# Channel_supply.net
KiCad netlist of a schematic drawn in Altium Designer
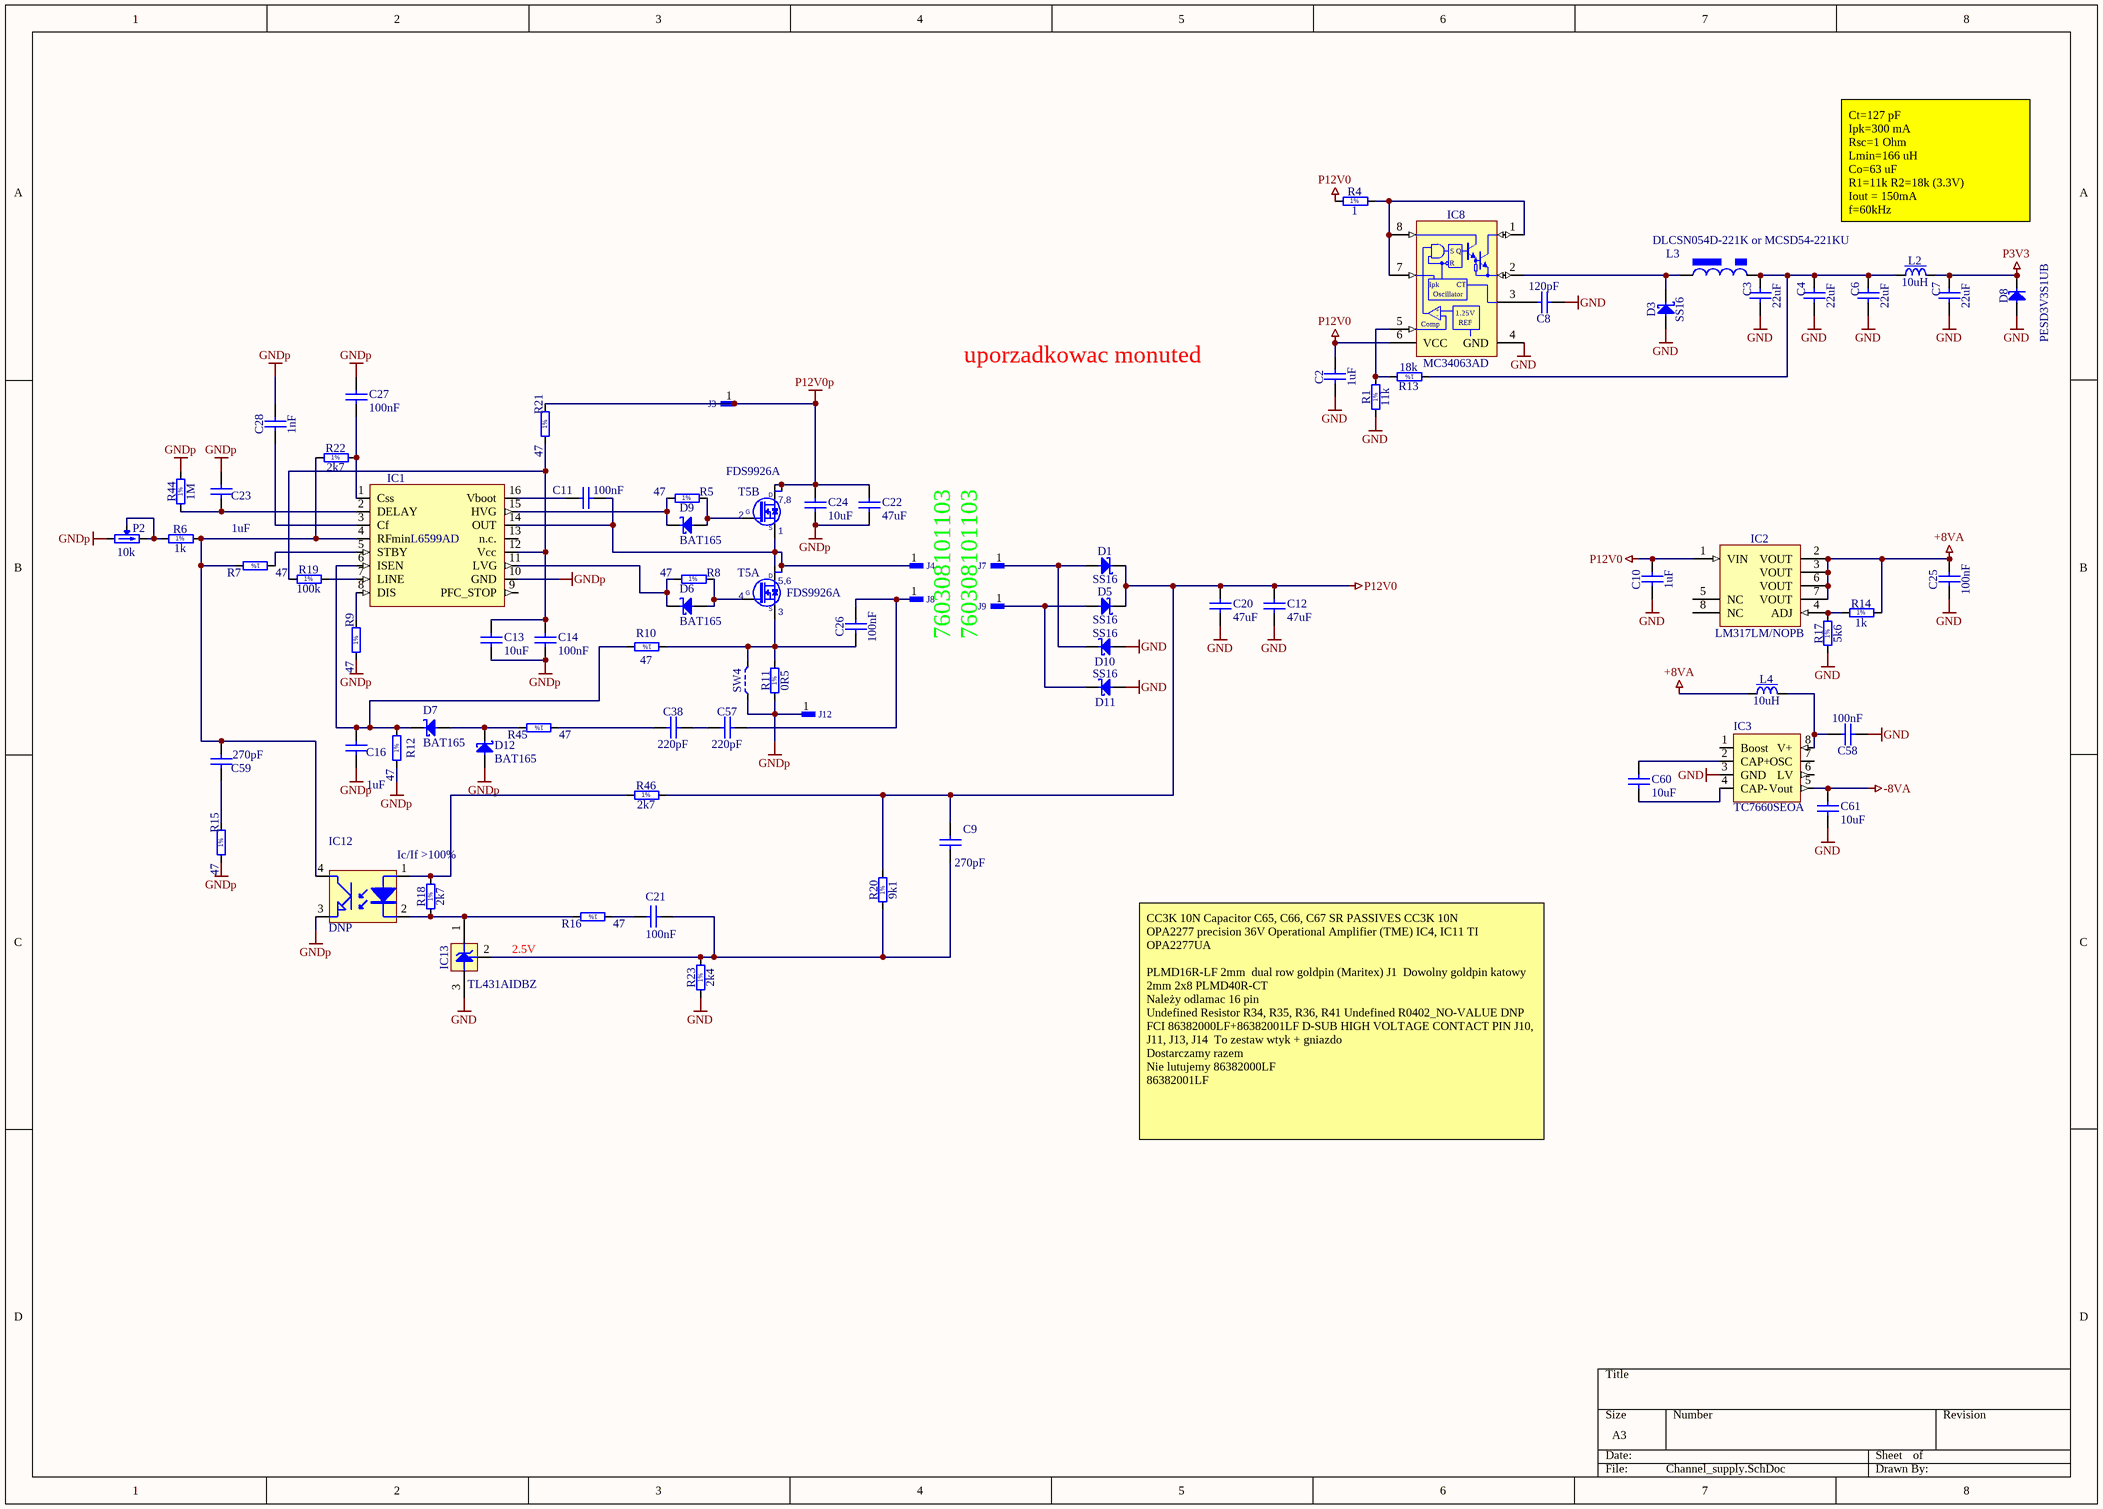
[diagram p0: Channel_supply.SchDoc]

(export (version "E")
  (design (tool "Eeschema 10.0.6"))
  (components
    (comp (ref "C2")
      (value "1uF")
      (footprint "CAPC1608X87N")
      (description "Non-polarised capacitor")
      (fields
        (field (name "PART NUMBER") "CC0603_1UF_25V_10%_X7R")
        (field (name "VOLTAGE") "25V")
        (field (name "AUTHOR") "CERN DEM JLC")
      )
      (libsource (lib "Capacitors") (part "Capacitor - non polarized"))
    )
    (comp (ref "C3")
      (value "22uF")
      (footprint "CAPC2012X135N")
      (description "Non-polarised capacitor")
      (fields
        (field (name "PART NUMBER") "CC0805_22UF_10V_+80%-20%_Y5V")
        (field (name "VOLTAGE") "10V")
        (field (name "AUTHOR") "CERN DEM JLC")
      )
      (libsource (lib "Capacitors") (part "Capacitor - non polarized"))
    )
    (comp (ref "C4")
      (value "22uF")
      (footprint "CAPC2012X135N")
      (description "Non-polarised capacitor")
      (fields
        (field (name "PART NUMBER") "CC0805_22UF_10V_+80%-20%_Y5V")
        (field (name "VOLTAGE") "10V")
        (field (name "AUTHOR") "CERN DEM JLC")
      )
      (libsource (lib "Capacitors") (part "Capacitor - non polarized"))
    )
    (comp (ref "C6")
      (value "22uF")
      (footprint "CAPC2012X135N")
      (description "Non-polarised capacitor")
      (fields
        (field (name "PART NUMBER") "CC0805_22UF_10V_+80%-20%_Y5V")
        (field (name "VOLTAGE") "10V")
        (field (name "AUTHOR") "CERN DEM JLC")
      )
      (libsource (lib "Capacitors") (part "Capacitor - non polarized"))
    )
    (comp (ref "C7")
      (value "22uF")
      (footprint "CAPC2012X135N")
      (description "Non-polarised capacitor")
      (fields
        (field (name "PART NUMBER") "CC0805_22UF_10V_+80%-20%_Y5V")
        (field (name "VOLTAGE") "10V")
        (field (name "AUTHOR") "CERN DEM JLC")
      )
      (libsource (lib "Capacitors") (part "Capacitor - non polarized"))
    )
    (comp (ref "C8")
      (value "120pF")
      (footprint "CAPC1005X55N")
      (description "Non-polarised capacitor")
      (fields
        (field (name "PART NUMBER") "CC0402_120PF_50V_5%_C0G")
        (field (name "VOLTAGE") "50V")
        (field (name "AUTHOR") "CERN DEM JLC")
      )
      (libsource (lib "Capacitors") (part "Capacitor - non polarized"))
    )
    (comp (ref "C9")
      (value "270pF")
      (footprint "CAPC1608X87N")
      (description "Non-polarised capacitor")
      (fields
        (field (name "PART NUMBER") "CC0603_270PF_50V_5%_NP0")
        (field (name "VOLTAGE") "50V")
        (field (name "AUTHOR") "CERN DEM JLC")
      )
      (libsource (lib "Capacitors") (part "Capacitor - non polarized"))
    )
    (comp (ref "C10")
      (value "1uF")
      (footprint "CAPC1608X87N")
      (description "Non-polarised capacitor")
      (fields
        (field (name "PART NUMBER") "CC0603_1UF_25V_10%_X7R")
        (field (name "VOLTAGE") "25V")
        (field (name "AUTHOR") "CERN DEM JLC")
      )
      (libsource (lib "Capacitors") (part "Capacitor - non polarized"))
    )
    (comp (ref "C11")
      (value "100nF")
      (footprint "CAPC1005X55N")
      (description "Non-polarised capacitor")
      (fields
        (field (name "PART NUMBER") "CC0402_100NF_16V_10%_X7R")
        (field (name "VOLTAGE") "16V")
        (field (name "AUTHOR") "CERN DEM JLC")
      )
      (libsource (lib "Capacitors") (part "Capacitor - non polarized"))
    )
    (comp (ref "C12")
      (value "47uF")
      (footprint "CAPC3216X180N")
      (description "Non-polarised capacitor")
      (fields
        (field (name "PART NUMBER") "CC1206_47UF_25V_20%_X5R")
        (field (name "VOLTAGE") "25V")
        (field (name "AUTHOR") "CERN DEM JLC")
      )
      (libsource (lib "Capacitors") (part "Capacitor - non polarized"))
    )
    (comp (ref "C13")
      (value "10uF")
      (footprint "CAPC3216X180N")
      (description "Non-polarised capacitor")
      (fields
        (field (name "PART NUMBER") "CC1206_10UF_25V_10%_X7R")
        (field (name "VOLTAGE") "25V")
        (field (name "AUTHOR") "CERN DEM JLC")
      )
      (libsource (lib "Capacitors") (part "Capacitor - non polarized"))
    )
    (comp (ref "C14")
      (value "100nF")
      (footprint "CAPC1005X55N")
      (description "Non-polarised capacitor")
      (fields
        (field (name "PART NUMBER") "CC0402_100NF_16V_10%_X7R")
        (field (name "VOLTAGE") "16V")
        (field (name "AUTHOR") "CERN DEM JLC")
      )
      (libsource (lib "Capacitors") (part "Capacitor - non polarized"))
    )
    (comp (ref "C16")
      (value "1uF")
      (footprint "CAPC1608X87N")
      (description "Non-polarised capacitor")
      (fields
        (field (name "PART NUMBER") "CC0603_1UF_25V_10%_X7R")
        (field (name "VOLTAGE") "25V")
        (field (name "AUTHOR") "CERN DEM JLC")
      )
      (libsource (lib "Capacitors") (part "Capacitor - non polarized"))
    )
    (comp (ref "C20")
      (value "47uF")
      (footprint "CAPC3216X180N")
      (description "Non-polarised capacitor")
      (fields
        (field (name "PART NUMBER") "CC1206_47UF_25V_20%_X5R")
        (field (name "VOLTAGE") "25V")
        (field (name "AUTHOR") "CERN DEM JLC")
      )
      (libsource (lib "Capacitors") (part "Capacitor - non polarized"))
    )
    (comp (ref "C21")
      (value "100nF")
      (footprint "CAPC1005X55N")
      (description "Non-polarised capacitor")
      (fields
        (field (name "PART NUMBER") "CC0402_100NF_16V_10%_X7R")
        (field (name "VOLTAGE") "16V")
        (field (name "AUTHOR") "CERN DEM JLC")
      )
      (libsource (lib "Capacitors") (part "Capacitor - non polarized"))
    )
    (comp (ref "C22")
      (value "47uF")
      (footprint "CAPC3216X180N")
      (description "Non-polarised capacitor")
      (fields
        (field (name "PART NUMBER") "CC1206_47UF_25V_20%_X5R")
        (field (name "VOLTAGE") "25V")
        (field (name "AUTHOR") "CERN DEM JLC")
      )
      (libsource (lib "Capacitors") (part "Capacitor - non polarized"))
    )
    (comp (ref "C23")
      (value "1uF")
      (footprint "CAPC1608X87N")
      (description "Non-polarised capacitor")
      (fields
        (field (name "PART NUMBER") "CC0603_1UF_25V_10%_X7R")
        (field (name "VOLTAGE") "25V")
        (field (name "AUTHOR") "CERN DEM JLC")
      )
      (libsource (lib "Capacitors") (part "Capacitor - non polarized"))
    )
    (comp (ref "C24")
      (value "10uF")
      (footprint "CAPC3216X180N")
      (description "Non-polarised capacitor")
      (fields
        (field (name "PART NUMBER") "CC1206_10UF_25V_10%_X7R")
        (field (name "VOLTAGE") "25V")
        (field (name "AUTHOR") "CERN DEM JLC")
      )
      (libsource (lib "Capacitors") (part "Capacitor - non polarized"))
    )
    (comp (ref "C25")
      (value "100nF")
      (footprint "CAPC1005X55N")
      (description "Non-polarised capacitor")
      (fields
        (field (name "PART NUMBER") "CC0402_100NF_16V_10%_X7R")
        (field (name "VOLTAGE") "16V")
        (field (name "AUTHOR") "CERN DEM JLC")
      )
      (libsource (lib "Capacitors") (part "Capacitor - non polarized"))
    )
    (comp (ref "C26")
      (value "100nF")
      (footprint "CAPC4532X250N")
      (description "Non-polarised capacitor")
      (fields
        (field (name "PART NUMBER") "CC1812_100NF_500V_10%_X7R")
        (field (name "VOLTAGE") "500V")
        (field (name "AUTHOR") "CERN DEM JMW")
      )
      (libsource (lib "Capacitors") (part "Capacitor - non polarized"))
    )
    (comp (ref "C27")
      (value "100nF")
      (footprint "CAPC1005X55N")
      (description "Non-polarised capacitor")
      (fields
        (field (name "PART NUMBER") "CC0402_100NF_16V_10%_X7R")
        (field (name "VOLTAGE") "16V")
        (field (name "AUTHOR") "CERN DEM JLC")
      )
      (libsource (lib "Capacitors") (part "Capacitor - non polarized"))
    )
    (comp (ref "C28")
      (value "1nF")
      (footprint "CAPC1608X90N")
      (description "Non-polarised capacitor")
      (fields
        (field (name "PART NUMBER") "CC0603_1NF_50V_5%_NP0")
        (field (name "VOLTAGE") "50V")
        (field (name "AUTHOR") "CERN DEM JLC")
      )
      (libsource (lib "Capacitors") (part "Capacitor - non polarized"))
    )
    (comp (ref "C38")
      (value "220pF")
      (footprint "CAPC3216X140N")
      (description "Non-polarised capacitor")
      (fields
        (field (name "PART NUMBER") "CC1206_220PF_100V_5%_NP0")
        (field (name "VOLTAGE") "100V")
        (field (name "AUTHOR") "CERN DEM JLC")
      )
      (libsource (lib "Capacitors") (part "Capacitor - non polarized"))
    )
    (comp (ref "C57")
      (value "220pF")
      (footprint "CAPC3216X140N")
      (description "Non-polarised capacitor")
      (fields
        (field (name "PART NUMBER") "CC1206_220PF_100V_5%_NP0")
        (field (name "VOLTAGE") "100V")
        (field (name "AUTHOR") "CERN DEM JLC")
      )
      (libsource (lib "Capacitors") (part "Capacitor - non polarized"))
    )
    (comp (ref "C58")
      (value "100nF")
      (footprint "CAPC1005X55N")
      (description "Non-polarised capacitor")
      (fields
        (field (name "PART NUMBER") "CC0402_100NF_16V_10%_X7R")
        (field (name "VOLTAGE") "16V")
        (field (name "AUTHOR") "CERN DEM JLC")
      )
      (libsource (lib "Capacitors") (part "Capacitor - non polarized"))
    )
    (comp (ref "C59")
      (value "270pF")
      (footprint "CAPC1608X87N")
      (description "Non-polarised capacitor")
      (fields
        (field (name "PART NUMBER") "CC0603_270PF_50V_5%_NP0")
        (field (name "VOLTAGE") "50V")
        (field (name "AUTHOR") "CERN DEM JLC")
      )
      (libsource (lib "Capacitors") (part "Capacitor - non polarized"))
    )
    (comp (ref "C60")
      (value "10uF")
      (footprint "CAPC3216X180N")
      (description "Non-polarised capacitor")
      (fields
        (field (name "PART NUMBER") "CC1206_10UF_25V_10%_X7R")
        (field (name "VOLTAGE") "25V")
        (field (name "AUTHOR") "CERN DEM JLC")
      )
      (libsource (lib "Capacitors") (part "Capacitor - non polarized"))
    )
    (comp (ref "C61")
      (value "10uF")
      (footprint "CAPC3216X180N")
      (description "Non-polarised capacitor")
      (fields
        (field (name "PART NUMBER") "CC1206_10UF_25V_10%_X7R")
        (field (name "VOLTAGE") "25V")
        (field (name "AUTHOR") "CERN DEM JLC")
      )
      (libsource (lib "Capacitors") (part "Capacitor - non polarized"))
    )
    (comp (ref "D1")
      (value "SS16")
      (footprint "DIOM5127X229N")
      (description "Schottky Diode")
      (fields
        (field (name "VOLTAGE") "60V")
        (field (name "POWER") "1A")
        (field (name "AUTHOR") "CERN DEM JLC")
      )
      (libsource (lib "ICs And Semiconductors") (part "Diode Schottky"))
    )
    (comp (ref "D3")
      (value "SS16")
      (footprint "DIOM5127X229N")
      (description "Schottky Diode")
      (fields
        (field (name "VOLTAGE") "60V")
        (field (name "POWER") "1A")
        (field (name "AUTHOR") "CERN DEM JLC")
      )
      (libsource (lib "ICs And Semiconductors") (part "Diode Schottky"))
    )
    (comp (ref "D5")
      (value "SS16")
      (footprint "DIOM5127X229N")
      (description "Schottky Diode")
      (fields
        (field (name "VOLTAGE") "60V")
        (field (name "POWER") "1A")
        (field (name "AUTHOR") "CERN DEM JLC")
      )
      (libsource (lib "ICs And Semiconductors") (part "Diode Schottky"))
    )
    (comp (ref "D6")
      (value "BAT165")
      (footprint "SOD2512X110N")
      (description "Schottky Diode")
      (fields
        (field (name "VOLTAGE") "40V")
        (field (name "POWER") "750mA")
        (field (name "AUTHOR") "CERN DEM JLC")
      )
      (libsource (lib "ICs And Semiconductors") (part "Diode Schottky"))
    )
    (comp (ref "D7")
      (value "BAT165")
      (footprint "SOD2512X110N")
      (description "Schottky Diode")
      (fields
        (field (name "VOLTAGE") "40V")
        (field (name "POWER") "750mA")
        (field (name "AUTHOR") "CERN DEM JLC")
      )
      (libsource (lib "ICs And Semiconductors") (part "Diode Schottky"))
    )
    (comp (ref "D8")
      (value "PESD3V3S1UB")
      (footprint "SODFL1608X65N")
      (description "ESD protection diode")
      (fields
        (field (name "VOLTAGE") "3V3")
        (field (name "POWER") "330W")
        (field (name "AUTHOR") "CERN DEM JLC")
      )
      (libsource (lib "ICs And Semiconductors") (part "Diode ESD"))
    )
    (comp (ref "D9")
      (value "BAT165")
      (footprint "SOD2512X110N")
      (description "Schottky Diode")
      (fields
        (field (name "VOLTAGE") "40V")
        (field (name "POWER") "750mA")
        (field (name "AUTHOR") "CERN DEM JLC")
      )
      (libsource (lib "ICs And Semiconductors") (part "Diode Schottky"))
    )
    (comp (ref "D10")
      (value "SS16")
      (footprint "DIOM5127X229N")
      (description "Schottky Diode")
      (fields
        (field (name "VOLTAGE") "60V")
        (field (name "POWER") "1A")
        (field (name "AUTHOR") "CERN DEM JLC")
      )
      (libsource (lib "ICs And Semiconductors") (part "Diode Schottky"))
    )
    (comp (ref "D11")
      (value "SS16")
      (footprint "DIOM5127X229N")
      (description "Schottky Diode")
      (fields
        (field (name "VOLTAGE") "60V")
        (field (name "POWER") "1A")
        (field (name "AUTHOR") "CERN DEM JLC")
      )
      (libsource (lib "ICs And Semiconductors") (part "Diode Schottky"))
    )
    (comp (ref "D12")
      (value "BAT165")
      (footprint "SOD2512X110N")
      (description "Schottky Diode")
      (fields
        (field (name "VOLTAGE") "40V")
        (field (name "POWER") "750mA")
        (field (name "AUTHOR") "CERN DEM JLC")
      )
      (libsource (lib "ICs And Semiconductors") (part "Diode Schottky"))
    )
    (comp (ref "IC1")
      (value "L6599AD")
      (footprint "SOIC127P600X175-16N")
      (description "Improved high voltage resonant LLC controller")
      (fields (field (name "MANUFACTURER") "ST MICROELECTRONICS") (field (name "AUTHOR") "GK"))
      (libsource (lib "LIBRARY_SCH") (part "PM_L6599"))
    )
    (comp (ref "IC2")
      (value "LM317LM/NOPB")
      (footprint "SOIC127P600X175-8N")
      (description "1.2V to 37V, 100mA Adjustable Positive Regulator")
      (fields (field (name "MANUFACTURER") "TEXAS INSTRUMENTS") (field (name "AUTHOR") "CERN DEM JLC"))
      (libsource (lib "ICs And Semiconductors") (part "LM317LM"))
    )
    (comp (ref "IC3")
      (value "TC7660SEOA")
      (footprint "SO-8")
      (description "20mA PUMP DC-TO-DC VOLTAGE CONVERTER")
      (libsource (lib "LIBRARY_SCH") (part "PM_TC7660"))
    )
    (comp (ref "IC8")
      (value "MC34063AD")
      (footprint "SOIC127P600X175-8N")
      (description "3V to 40V 1.5A Peak Boost/Buck/Inverting Switching Regulator")
      (fields (field (name "MANUFACTURER") "TEXAS INSTRUMENTS") (field (name "AUTHOR") "CERN DEM JLC"))
      (libsource (lib "ICs And Semiconductors") (part "MC34063A"))
    )
    (comp (ref "IC12")
      (value "DNP")
      (footprint "OPI1264C")
      (description "10kV opto-coupler")
      (libsource (lib "LIBRARY_SCH") (part "OPTO-OPI1264C"))
    )
    (comp (ref "IC13")
      (value "TL431AIDBZ")
      (footprint "SOT95P237X112-3N")
      (description "Precision Reference 1=Cathode 2=Adj 3=Anode")
      (fields (field (name "MANUFACTURER") "TEXAS INSTRUMENTS") (field (name "AUTHOR") "CERN DEM JMW"))
      (libsource (lib "ICs And Semiconductors") (part "VREF 1C-2ADJ-3A"))
    )
    (comp (ref "J3")
      (value "SMD Pad")
      (footprint "R400X300")
      (description "Single SMD Pad")
      (fields (field (name "PART NUMBER") "SMD_PAD_4X3MM") (field (name "AUTHOR") "CERN DEM JLC"))
      (libsource (lib "Eletro-mechanical") (part "Single SMD Pad"))
    )
    (comp (ref "J4")
      (value "SMD Pad")
      (footprint "R400X300")
      (description "Single SMD Pad")
      (fields (field (name "PART NUMBER") "SMD_PAD_4X3MM") (field (name "AUTHOR") "CERN DEM JLC"))
      (libsource (lib "") (part "Single SMD Pad_1"))
    )
    (comp (ref "J7")
      (value "SMD Pad")
      (footprint "R400X300")
      (description "Single SMD Pad")
      (fields (field (name "PART NUMBER") "SMD_PAD_4X3MM") (field (name "AUTHOR") "CERN DEM JLC"))
      (libsource (lib "Eletro-mechanical") (part "Single SMD Pad"))
    )
    (comp (ref "J8")
      (value "SMD Pad")
      (footprint "R400X300")
      (description "Single SMD Pad")
      (fields (field (name "PART NUMBER") "SMD_PAD_4X3MM") (field (name "AUTHOR") "CERN DEM JLC"))
      (libsource (lib "") (part "Single SMD Pad_1"))
    )
    (comp (ref "J9")
      (value "SMD Pad")
      (footprint "R400X300")
      (description "Single SMD Pad")
      (fields (field (name "PART NUMBER") "SMD_PAD_4X3MM") (field (name "AUTHOR") "CERN DEM JLC"))
      (libsource (lib "Eletro-mechanical") (part "Single SMD Pad"))
    )
    (comp (ref "J12")
      (value "SMD Pad")
      (footprint "R400X300")
      (description "Single SMD Pad")
      (fields (field (name "PART NUMBER") "SMD_PAD_4X3MM") (field (name "AUTHOR") "CERN DEM JLC"))
      (libsource (lib "") (part "Single SMD Pad_1"))
    )
    (comp (ref "L2")
      (value "10uH")
      (footprint "INDM3225X210N")
      (description "Inductor With Core")
      (fields
        (field (name "PART NUMBER") "IND1210_10UH_10%_EPCOS_B82422A")
        (field (name "POWER") "180mA")
        (field (name "AUTHOR") "CERN DEM BC")
      )
      (libsource (lib "Inductors & Transformers") (part "Inductor With Magnetic core"))
    )
    (comp (ref "L3")
      (value "DLCSN054D-221K or MCSD54-221KU")
      (footprint "L_CSN054D")
      (description "220uH, 0.35A, 1.57R, inductor (Maritex)")
      (libsource (lib "LIBRARY_SCH") (part "L_POWER_DLCSN054D_220uH"))
    )
    (comp (ref "L4")
      (value "10uH")
      (footprint "INDM3225X210N")
      (description "Inductor With Core")
      (fields
        (field (name "PART NUMBER") "IND1210_10UH_10%_EPCOS_B82422A")
        (field (name "POWER") "180mA")
        (field (name "AUTHOR") "CERN DEM BC")
      )
      (libsource (lib "Inductors & Transformers") (part "Inductor With Magnetic core"))
    )
    (comp (ref "P2")
      (value "10k")
      (footprint "TRIM_BOURNS_3314G-1")
      (description "Trimming Potentiometer")
      (fields
        (field (name "PART NUMBER") "TRIM_1T_10K_BOURNS_3314G-1-103E")
        (field (name "POWER") "0.25W")
        (field (name "AUTHOR") "CERN DEM JLC")
      )
      (libsource (lib "Resistors") (part "Trimming Potentiometer"))
    )
    (comp (ref "R1")
      (value "11k")
      (footprint "RESC1005X40N")
      (description "Resistor - 1%")
      (fields
        (field (name "PART NUMBER") "R0402_11K_1%_0.0625W_100PPM")
        (field (name "POWER") "0.0625W")
        (field (name "AUTHOR") "CERN DEM JLC")
      )
      (libsource (lib "Resistors") (part "Resistor - 1%"))
    )
    (comp (ref "R4")
      (value "1")
      (footprint "RESC1608X55N")
      (description "Resistor - 1%")
      (fields
        (field (name "PART NUMBER") "R0603_1R_1%_0.1W_200PPM")
        (field (name "POWER") "0.1W")
        (field (name "AUTHOR") "CERN DEM JLC")
      )
      (libsource (lib "Resistors") (part "Resistor - 1%"))
    )
    (comp (ref "R5")
      (value "47")
      (footprint "RESC1608X55N")
      (description "Resistor - 1%")
      (fields
        (field (name "PART NUMBER") "R0603_47R_1%_0.1W_100PPM")
        (field (name "POWER") "0.1W")
        (field (name "AUTHOR") "CERN DEM JLC")
      )
      (libsource (lib "Resistors") (part "Resistor - 1%"))
    )
    (comp (ref "R6")
      (value "1k")
      (footprint "RESC1005X40N")
      (description "Resistor - 1%")
      (fields
        (field (name "PART NUMBER") "R0402_1K_1%_0.0625W_100PPM")
        (field (name "POWER") "0.0625W")
        (field (name "AUTHOR") "CERN DEM JLC")
      )
      (libsource (lib "Resistors") (part "Resistor - 1%"))
    )
    (comp (ref "R7")
      (value "47")
      (footprint "RESC1608X55N")
      (description "Resistor - 1%")
      (fields
        (field (name "PART NUMBER") "R0603_47R_1%_0.1W_100PPM")
        (field (name "POWER") "0.1W")
        (field (name "AUTHOR") "CERN DEM JLC")
      )
      (libsource (lib "Resistors") (part "Resistor - 1%"))
    )
    (comp (ref "R8")
      (value "47")
      (footprint "RESC1608X55N")
      (description "Resistor - 1%")
      (fields
        (field (name "PART NUMBER") "R0603_47R_1%_0.1W_100PPM")
        (field (name "POWER") "0.1W")
        (field (name "AUTHOR") "CERN DEM JLC")
      )
      (libsource (lib "Resistors") (part "Resistor - 1%"))
    )
    (comp (ref "R9")
      (value "47")
      (footprint "RESC1608X55N")
      (description "Resistor - 1%")
      (fields
        (field (name "PART NUMBER") "R0603_47R_1%_0.1W_100PPM")
        (field (name "POWER") "0.1W")
        (field (name "AUTHOR") "CERN DEM JLC")
      )
      (libsource (lib "Resistors") (part "Resistor - 1%"))
    )
    (comp (ref "R10")
      (value "47")
      (footprint "RESC1608X55N")
      (description "Resistor - 1%")
      (fields
        (field (name "PART NUMBER") "R0603_47R_1%_0.1W_100PPM")
        (field (name "POWER") "0.1W")
        (field (name "AUTHOR") "CERN DEM JLC")
      )
      (libsource (lib "Resistors") (part "Resistor - 1%"))
    )
    (comp (ref "R11")
      (value "0R5")
      (footprint "RESC6532X80N")
      (description "Resistor - 1%")
      (fields
        (field (name "PART NUMBER") "R2512_0R5_1%_1.5W_100PPM")
        (field (name "POWER") "1.5W")
        (field (name "AUTHOR") "CERN DEM JLC")
      )
      (libsource (lib "Resistors") (part "Resistor - 1%"))
    )
    (comp (ref "R12")
      (value "47")
      (footprint "RESC1608X55N")
      (description "Resistor - 1%")
      (fields
        (field (name "PART NUMBER") "R0603_47R_1%_0.1W_100PPM")
        (field (name "POWER") "0.1W")
        (field (name "AUTHOR") "CERN DEM JLC")
      )
      (libsource (lib "Resistors") (part "Resistor - 1%"))
    )
    (comp (ref "R13")
      (value "18k")
      (footprint "RESC1005X40N")
      (description "Resistor - 1%")
      (fields
        (field (name "PART NUMBER") "R0402_18K_1%_0.0625W_100PPM")
        (field (name "POWER") "0.0625W")
        (field (name "AUTHOR") "CERN DEM JLC")
      )
      (libsource (lib "Resistors") (part "Resistor - 1%"))
    )
    (comp (ref "R14")
      (value "1k")
      (footprint "RESC1005X40N")
      (description "Resistor - 1%")
      (fields
        (field (name "PART NUMBER") "R0402_1K_1%_0.0625W_100PPM")
        (field (name "POWER") "0.0625W")
        (field (name "AUTHOR") "CERN DEM JLC")
      )
      (libsource (lib "Resistors") (part "Resistor - 1%"))
    )
    (comp (ref "R15")
      (value "47")
      (footprint "RESC1608X55N")
      (description "Resistor - 1%")
      (fields
        (field (name "PART NUMBER") "R0603_47R_1%_0.1W_100PPM")
        (field (name "POWER") "0.1W")
        (field (name "AUTHOR") "CERN DEM JLC")
      )
      (libsource (lib "Resistors") (part "Resistor - 1%"))
    )
    (comp (ref "R16")
      (value "47")
      (footprint "RESC1608X55N")
      (description "Resistor - 1%")
      (fields
        (field (name "PART NUMBER") "R0603_47R_1%_0.1W_100PPM")
        (field (name "POWER") "0.1W")
        (field (name "AUTHOR") "CERN DEM JLC")
      )
      (libsource (lib "Resistors") (part "Resistor - 1%"))
    )
    (comp (ref "R17")
      (value "5k6")
      (footprint "RESC1005X40N")
      (description "Resistor - 1%")
      (fields
        (field (name "PART NUMBER") "R0402_5K6_1%_0.0625W_100PPM")
        (field (name "POWER") "0.0625W")
        (field (name "AUTHOR") "CERN DEM JLC")
      )
      (libsource (lib "Resistors") (part "Resistor - 1%"))
    )
    (comp (ref "R18")
      (value "2k7")
      (footprint "RESC1608X55N")
      (description "Resistor - 1%")
      (fields
        (field (name "PART NUMBER") "R0603_2K7_1%_0.1W_100PPM")
        (field (name "POWER") "0.1W")
        (field (name "AUTHOR") "CERN DEM JLC")
      )
      (libsource (lib "Resistors") (part "Resistor - 1%"))
    )
    (comp (ref "R19")
      (value "100k")
      (footprint "RESC1005X40N")
      (description "Resistor - 1%")
      (fields
        (field (name "PART NUMBER") "R0402_100K_1%_0.0625W_100PPM")
        (field (name "POWER") "0.0625W")
        (field (name "AUTHOR") "CERN DEM JLC")
      )
      (libsource (lib "Resistors") (part "Resistor - 1%"))
    )
    (comp (ref "R20")
      (value "9k1")
      (footprint "RESC1608X55N")
      (description "Resistor - 1%")
      (fields
        (field (name "PART NUMBER") "R0603_9K1_1%_0.1W_100PPM")
        (field (name "POWER") "0.1W")
        (field (name "AUTHOR") "CERN DEM JLC")
      )
      (libsource (lib "Resistors") (part "Resistor - 1%"))
    )
    (comp (ref "R21")
      (value "47")
      (footprint "RESC1608X55N")
      (description "Resistor - 1%")
      (fields
        (field (name "PART NUMBER") "R0603_47R_1%_0.1W_100PPM")
        (field (name "POWER") "0.1W")
        (field (name "AUTHOR") "CERN DEM JLC")
      )
      (libsource (lib "Resistors") (part "Resistor - 1%"))
    )
    (comp (ref "R22")
      (value "2k7")
      (footprint "RESC1608X55N")
      (description "Resistor - 1%")
      (fields
        (field (name "PART NUMBER") "R0603_2K7_1%_0.1W_100PPM")
        (field (name "POWER") "0.1W")
        (field (name "AUTHOR") "CERN DEM JLC")
      )
      (libsource (lib "Resistors") (part "Resistor - 1%"))
    )
    (comp (ref "R23")
      (value "2k4")
      (footprint "RESC1608X55N")
      (description "Resistor - 1%")
      (fields
        (field (name "PART NUMBER") "R0603_2K4_1%_0.1W_100PPM")
        (field (name "POWER") "0.1W")
        (field (name "AUTHOR") "CERN DEM JLC")
      )
      (libsource (lib "Resistors") (part "Resistor - 1%"))
    )
    (comp (ref "R44")
      (value "1M")
      (footprint "RESC1608X55N")
      (description "Resistor - 1%")
      (fields
        (field (name "PART NUMBER") "R0603_1M_1%_0.1W_100PPM")
        (field (name "POWER") "0.1W")
        (field (name "AUTHOR") "CERN DEM JLC")
      )
      (libsource (lib "Resistors") (part "Resistor - 1%"))
    )
    (comp (ref "R45")
      (value "47")
      (footprint "RESC1608X55N")
      (description "Resistor - 1%")
      (fields
        (field (name "PART NUMBER") "R0603_47R_1%_0.1W_100PPM")
        (field (name "POWER") "0.1W")
        (field (name "AUTHOR") "CERN DEM JLC")
      )
      (libsource (lib "Resistors") (part "Resistor - 1%"))
    )
    (comp (ref "R46")
      (value "2k7")
      (footprint "RESC1608X55N")
      (description "Resistor - 1%")
      (fields
        (field (name "PART NUMBER") "R0603_2K7_1%_0.1W_100PPM")
        (field (name "POWER") "0.1W")
        (field (name "AUTHOR") "CERN DEM JLC")
      )
      (libsource (lib "Resistors") (part "Resistor - 1%"))
    )
    (comp (ref "SW4")
      (value "Switch")
      (footprint "JUMPSMD0805_G50")
      (description "2 SMD Pads for Bound by Solder  Drop")
      (fields
        (field (name "PART NUMBER") "JUMPSMD0805_G50")
        (field (name "MANUFACTURER") "None")
        (field (name "AUTHOR") "CERN DEM JLC")
      )
      (libsource (lib "Eletro-mechanical") (part "SMD Solder Jumper"))
    )
    (comp (ref "T5")
      (value "FDS9926A")
      (footprint "SOIC127P600X175-8N")
      (description "20V DUAL N-Channel 2.5V Specified PowerTrench MOSFET")
      (fields (field (name "MANUFACTURER") "FAIRCHILD SEMICONDUCTOR") (field (name "AUTHOR") "CERN DEM BC"))
      (libsource (lib "ICs And Semiconductors") (part "FDS9926A"))
    )
  )
  (nets
    (net (code "1") (name "+8VA") (class "Default")
      (node (ref "C25") (pin "2") (pinfunction "2_2") (pintype "passive"))
      (node (ref "IC2") (pin "2") (pinfunction "VOUT_2") (pintype "power_in"))
      (node (ref "IC2") (pin "3") (pinfunction "VOUT_3") (pintype "power_in"))
      (node (ref "IC2") (pin "6") (pinfunction "VOUT_6") (pintype "power_in"))
      (node (ref "IC2") (pin "7") (pinfunction "VOUT_7") (pintype "power_in"))
      (node (ref "L4") (pin "1") (pinfunction "1_1") (pintype "passive"))
      (node (ref "R14") (pin "2") (pinfunction "2_2") (pintype "passive"))
    )
    (net (code "2") (name "-8VA") (class "Default")
      (node (ref "C61") (pin "1") (pinfunction "1_1") (pintype "passive"))
      (node (ref "IC3") (pin "5") (pinfunction "Vout_5") (pintype "output"))
    )
    (net (code "3") (name "GND") (class "Default")
      (node (ref "C10") (pin "1") (pinfunction "1_1") (pintype "passive"))
      (node (ref "C12") (pin "2") (pinfunction "2_2") (pintype "passive"))
      (node (ref "C2") (pin "1") (pinfunction "1_1") (pintype "passive"))
      (node (ref "C20") (pin "2") (pinfunction "2_2") (pintype "passive"))
      (node (ref "C25") (pin "1") (pinfunction "1_1") (pintype "passive"))
      (node (ref "C3") (pin "1") (pinfunction "1_1") (pintype "passive"))
      (node (ref "C4") (pin "1") (pinfunction "1_1") (pintype "passive"))
      (node (ref "C58") (pin "1") (pinfunction "1_1") (pintype "passive"))
      (node (ref "C6") (pin "1") (pinfunction "1_1") (pintype "passive"))
      (node (ref "C61") (pin "2") (pinfunction "2_2") (pintype "passive"))
      (node (ref "C7") (pin "1") (pinfunction "1_1") (pintype "passive"))
      (node (ref "C8") (pin "1") (pinfunction "1_1") (pintype "passive"))
      (node (ref "D10") (pin "2") (pinfunction "A_2") (pintype "passive"))
      (node (ref "D11") (pin "2") (pinfunction "A_2") (pintype "passive"))
      (node (ref "D3") (pin "2") (pinfunction "A_2") (pintype "passive"))
      (node (ref "D8") (pin "2") (pinfunction "A_2") (pintype "passive"))
      (node (ref "IC13") (pin "3") (pinfunction "A_3") (pintype "passive"))
      (node (ref "IC3") (pin "3") (pinfunction "GND_3") (pintype "power_in"))
      (node (ref "IC8") (pin "4") (pinfunction "GND_4") (pintype "power_in"))
      (node (ref "R1") (pin "1") (pinfunction "1_1") (pintype "passive"))
      (node (ref "R17") (pin "1") (pinfunction "1_1") (pintype "passive"))
      (node (ref "R23") (pin "1") (pinfunction "1_1") (pintype "passive"))
    )
    (net (code "4") (name "GNDp") (class "Default")
      (node (ref "C13") (pin "2") (pinfunction "2_2") (pintype "passive"))
      (node (ref "C14") (pin "2") (pinfunction "2_2") (pintype "passive"))
      (node (ref "C16") (pin "1") (pinfunction "1_1") (pintype "passive"))
      (node (ref "C22") (pin "2") (pinfunction "2_2") (pintype "passive"))
      (node (ref "C23") (pin "2") (pinfunction "2_2") (pintype "passive"))
      (node (ref "C24") (pin "2") (pinfunction "2_2") (pintype "passive"))
      (node (ref "C27") (pin "1") (pinfunction "1_1") (pintype "passive"))
      (node (ref "C28") (pin "2") (pinfunction "2_2") (pintype "passive"))
      (node (ref "D12") (pin "2") (pinfunction "A_2") (pintype "passive"))
      (node (ref "IC1") (pin "10") (pinfunction "GND_10") (pintype "power_in"))
      (node (ref "IC12") (pin "3") (pinfunction "E_3") (pintype "passive"))
      (node (ref "J12") (pin "1") (pinfunction "1_1") (pintype "bidirectional"))
      (node (ref "P2") (pin "1") (pinfunction "CCW_1") (pintype "passive"))
      (node (ref "R11") (pin "1") (pinfunction "1_1") (pintype "passive"))
      (node (ref "R12") (pin "1") (pinfunction "1_1") (pintype "passive"))
      (node (ref "R15") (pin "1") (pinfunction "1_1") (pintype "passive"))
      (node (ref "R44") (pin "2") (pinfunction "2_2") (pintype "passive"))
      (node (ref "R9") (pin "1") (pinfunction "1_1") (pintype "passive"))
      (node (ref "SW4") (pin "1") (pinfunction "1_1") (pintype "passive"))
    )
    (net (code "5") (name "Net-(C3-Pad2)") (class "Default")
      (node (ref "C3") (pin "2") (pinfunction "2_2") (pintype "passive"))
      (node (ref "C4") (pin "2") (pinfunction "2_2") (pintype "passive"))
      (node (ref "C6") (pin "2") (pinfunction "2_2") (pintype "passive"))
      (node (ref "L2") (pin "1") (pinfunction "1_1") (pintype "passive"))
      (node (ref "L3") (pin "2") (pintype "passive"))
      (node (ref "R13") (pin "1") (pinfunction "1_1") (pintype "passive"))
    )
    (net (code "6") (name "Net-(C21-Pad2)") (class "Default")
      (node (ref "C21") (pin "2") (pinfunction "2_2") (pintype "passive"))
      (node (ref "R16") (pin "1") (pinfunction "1_1") (pintype "passive"))
    )
    (net (code "7") (name "Net-(C26-Pad2)") (class "Default")
      (node (ref "C26") (pin "2") (pinfunction "2_2") (pintype "passive"))
      (node (ref "C57") (pin "2") (pinfunction "2_2") (pintype "passive"))
      (node (ref "J8") (pin "1") (pinfunction "1_1") (pintype "bidirectional"))
    )
    (net (code "8") (name "Net-(C38-Pad1)") (class "Default")
      (node (ref "C38") (pin "1") (pinfunction "1_1") (pintype "passive"))
      (node (ref "R45") (pin "1") (pinfunction "1_1") (pintype "passive"))
    )
    (net (code "9") (name "Net-(C38-Pad2)") (class "Default")
      (node (ref "C38") (pin "2") (pinfunction "2_2") (pintype "passive"))
      (node (ref "C57") (pin "1") (pinfunction "1_1") (pintype "passive"))
    )
    (net (code "10") (name "Net-(C59-Pad1)") (class "Default")
      (node (ref "C59") (pin "1") (pinfunction "1_1") (pintype "passive"))
      (node (ref "R15") (pin "2") (pinfunction "2_2") (pintype "passive"))
    )
    (net (code "11") (name "Net-(D1-A)") (class "Default")
      (node (ref "D1") (pin "2") (pinfunction "A_2") (pintype "passive"))
      (node (ref "D10") (pin "1") (pinfunction "C_1") (pintype "passive"))
      (node (ref "J7") (pin "1") (pinfunction "1_1") (pintype "bidirectional"))
    )
    (net (code "12") (name "Net-(D3-C)") (class "Default")
      (node (ref "D3") (pin "1") (pinfunction "C_1") (pintype "passive"))
      (node (ref "IC8") (pin "2") (pinfunction "SWE_2") (pintype "bidirectional"))
      (node (ref "L3") (pin "1") (pintype "passive"))
    )
    (net (code "13") (name "Net-(D6-A)") (class "Default")
      (node (ref "D6") (pin "2") (pinfunction "A_2") (pintype "passive"))
      (node (ref "R8") (pin "2") (pinfunction "2_2") (pintype "passive"))
      (node (ref "T5") (pin "4") (pinfunction "G_4") (pintype "passive"))
    )
    (net (code "14") (name "Net-(D6-C)") (class "Default")
      (node (ref "D6") (pin "1") (pinfunction "C_1") (pintype "passive"))
      (node (ref "IC1") (pin "11") (pinfunction "LVG_11") (pintype "output"))
      (node (ref "R8") (pin "1") (pinfunction "1_1") (pintype "passive"))
    )
    (net (code "15") (name "Net-(D7-C)") (class "Default")
      (node (ref "C16") (pin "2") (pinfunction "2_2") (pintype "passive"))
      (node (ref "D7") (pin "1") (pinfunction "C_1") (pintype "passive"))
      (node (ref "IC1") (pin "6") (pinfunction "ISEN_6") (pintype "input"))
      (node (ref "R10") (pin "2") (pinfunction "2_2") (pintype "passive"))
      (node (ref "R12") (pin "2") (pinfunction "2_2") (pintype "passive"))
    )
    (net (code "16") (name "Net-(D9-A)") (class "Default")
      (node (ref "D9") (pin "2") (pinfunction "A_2") (pintype "passive"))
      (node (ref "R5") (pin "2") (pinfunction "2_2") (pintype "passive"))
      (node (ref "T5") (pin "2") (pinfunction "G_2") (pintype "passive"))
    )
    (net (code "17") (name "Net-(D9-C)") (class "Default")
      (node (ref "D9") (pin "1") (pinfunction "C_1") (pintype "passive"))
      (node (ref "IC1") (pin "15") (pinfunction "HVG_15") (pintype "output"))
      (node (ref "R5") (pin "1") (pinfunction "1_1") (pintype "passive"))
    )
    (net (code "18") (name "Net-(D11-C)") (class "Default")
      (node (ref "D11") (pin "1") (pinfunction "C_1") (pintype "passive"))
      (node (ref "D5") (pin "2") (pinfunction "A_2") (pintype "passive"))
      (node (ref "J9") (pin "1") (pinfunction "1_1") (pintype "bidirectional"))
    )
    (net (code "19") (name "Net-(D12-C)") (class "Default")
      (node (ref "D12") (pin "1") (pinfunction "C_1") (pintype "passive"))
      (node (ref "D7") (pin "2") (pinfunction "A_2") (pintype "passive"))
      (node (ref "R45") (pin "2") (pinfunction "2_2") (pintype "passive"))
    )
    (net (code "20") (name "Net-(IC1-Cf)") (class "Default")
      (node (ref "C28") (pin "1") (pinfunction "1_1") (pintype "passive"))
      (node (ref "IC1") (pin "3") (pinfunction "Cf_3") (pintype "passive"))
    )
    (net (code "21") (name "Net-(IC1-Css)") (class "Default")
      (node (ref "C27") (pin "2") (pinfunction "2_2") (pintype "passive"))
      (node (ref "IC1") (pin "1") (pinfunction "Css_1") (pintype "passive"))
      (node (ref "R22") (pin "2") (pinfunction "2_2") (pintype "passive"))
    )
    (net (code "22") (name "Net-(IC1-DELAY)") (class "Default")
      (node (ref "C23") (pin "1") (pinfunction "1_1") (pintype "passive"))
      (node (ref "IC1") (pin "2") (pinfunction "DELAY_2") (pintype "passive"))
      (node (ref "R44") (pin "1") (pinfunction "1_1") (pintype "passive"))
    )
    (net (code "23") (name "Net-(IC1-DIS)") (class "Default")
      (node (ref "IC1") (pin "8") (pinfunction "DIS_8") (pintype "input"))
      (node (ref "R9") (pin "2") (pinfunction "2_2") (pintype "passive"))
    )
    (net (code "24") (name "Net-(IC1-LINE)") (class "Default")
      (node (ref "IC1") (pin "7") (pinfunction "LINE_7") (pintype "input"))
      (node (ref "R19") (pin "2") (pinfunction "2_2") (pintype "passive"))
    )
    (net (code "25") (name "Net-(IC1-OUT)") (class "Default")
      (node (ref "C11") (pin "2") (pinfunction "2_2") (pintype "passive"))
      (node (ref "IC1") (pin "14") (pinfunction "OUT_14") (pintype "passive"))
      (node (ref "J4") (pin "1") (pinfunction "1_1") (pintype "bidirectional"))
      (node (ref "T5") (pin "1") (pinfunction "S_1") (pintype "passive"))
      (node (ref "T5") (pin "5") (pinfunction "D_5") (pintype "passive"))
      (node (ref "T5") (pin "6") (pinfunction "D_6") (pintype "passive"))
    )
    (net (code "26") (name "Net-(IC1-RFmin)") (class "Default")
      (node (ref "C59") (pin "2") (pinfunction "2_2") (pintype "passive"))
      (node (ref "IC1") (pin "4") (pinfunction "RFmin_4") (pintype "passive"))
      (node (ref "IC12") (pin "4") (pinfunction "C_4") (pintype "passive"))
      (node (ref "R22") (pin "1") (pinfunction "1_1") (pintype "passive"))
      (node (ref "R6") (pin "2") (pinfunction "2_2") (pintype "passive"))
      (node (ref "R7") (pin "2") (pinfunction "2_2") (pintype "passive"))
    )
    (net (code "27") (name "Net-(IC1-STBY)") (class "Default")
      (node (ref "IC1") (pin "5") (pinfunction "STBY_5") (pintype "input"))
      (node (ref "R7") (pin "1") (pinfunction "1_1") (pintype "passive"))
    )
    (net (code "28") (name "Net-(IC1-Vboot)") (class "Default")
      (node (ref "C11") (pin "1") (pinfunction "1_1") (pintype "passive"))
      (node (ref "IC1") (pin "16") (pinfunction "Vboot_16") (pintype "power_in"))
    )
    (net (code "29") (name "Net-(IC1-Vcc)") (class "Default")
      (node (ref "C13") (pin "1") (pinfunction "1_1") (pintype "passive"))
      (node (ref "C14") (pin "1") (pinfunction "1_1") (pintype "passive"))
      (node (ref "IC1") (pin "12") (pinfunction "Vcc_12") (pintype "power_in"))
      (node (ref "R19") (pin "1") (pinfunction "1_1") (pintype "passive"))
      (node (ref "R21") (pin "1") (pinfunction "1_1") (pintype "passive"))
    )
    (net (code "30") (name "Net-(IC2-ADJ)") (class "Default")
      (node (ref "IC2") (pin "4") (pinfunction "ADJ_4") (pintype "input"))
      (node (ref "R14") (pin "1") (pinfunction "1_1") (pintype "passive"))
      (node (ref "R17") (pin "2") (pinfunction "2_2") (pintype "passive"))
    )
    (net (code "31") (name "Net-(IC3-CAP+)") (class "Default")
      (node (ref "C60") (pin "1") (pinfunction "1_1") (pintype "passive"))
      (node (ref "IC3") (pin "2") (pinfunction "CAP+_2") (pintype "passive"))
    )
    (net (code "32") (name "Net-(IC3-CAP-)") (class "Default")
      (node (ref "C60") (pin "2") (pinfunction "2_2") (pintype "passive"))
      (node (ref "IC3") (pin "4") (pinfunction "CAP-_4") (pintype "power_in"))
    )
    (net (code "33") (name "Net-(IC3-V+)") (class "Default")
      (node (ref "C58") (pin "2") (pinfunction "2_2") (pintype "passive"))
      (node (ref "IC3") (pin "8") (pinfunction "V+_8") (pintype "input"))
      (node (ref "L4") (pin "2") (pinfunction "2_2") (pintype "passive"))
    )
    (net (code "34") (name "Net-(IC8-COMP)") (class "Default")
      (node (ref "IC8") (pin "5") (pinfunction "COMP_5") (pintype "input"))
      (node (ref "R1") (pin "2") (pinfunction "2_2") (pintype "passive"))
      (node (ref "R13") (pin "2") (pinfunction "2_2") (pintype "passive"))
    )
    (net (code "35") (name "Net-(IC8-DRVC)") (class "Default")
      (node (ref "IC8") (pin "1") (pinfunction "SWC_1") (pintype "bidirectional"))
      (node (ref "IC8") (pin "7") (pinfunction "Ipk_7") (pintype "input"))
      (node (ref "IC8") (pin "8") (pinfunction "DRVC_8") (pintype "input"))
      (node (ref "R4") (pin "2") (pinfunction "2_2") (pintype "passive"))
    )
    (net (code "36") (name "Net-(IC8-TC)") (class "Default")
      (node (ref "C8") (pin "2") (pinfunction "2_2") (pintype "passive"))
      (node (ref "IC8") (pin "3") (pinfunction "TC_3") (pintype "passive"))
    )
    (net (code "37") (name "Net-(IC12-A)") (class "Default")
      (node (ref "IC12") (pin "1") (pinfunction "A_1") (pintype "passive"))
      (node (ref "R18") (pin "2") (pinfunction "2_2") (pintype "passive"))
      (node (ref "R46") (pin "1") (pinfunction "1_1") (pintype "passive"))
    )
    (net (code "38") (name "Net-(IC12-K)") (class "Default")
      (node (ref "IC12") (pin "2") (pinfunction "K_2") (pintype "passive"))
      (node (ref "IC13") (pin "1") (pinfunction "C_1") (pintype "passive"))
      (node (ref "R16") (pin "2") (pinfunction "2_2") (pintype "passive"))
      (node (ref "R18") (pin "1") (pinfunction "1_1") (pintype "passive"))
    )
    (net (code "39") (name "Net-(IC13-Adj)") (class "Default")
      (node (ref "C21") (pin "1") (pinfunction "1_1") (pintype "passive"))
      (node (ref "C9") (pin "1") (pinfunction "1_1") (pintype "passive"))
      (node (ref "IC13") (pin "2") (pinfunction "Adj_2") (pintype "passive"))
      (node (ref "R20") (pin "1") (pinfunction "1_1") (pintype "passive"))
      (node (ref "R23") (pin "2") (pinfunction "2_2") (pintype "passive"))
    )
    (net (code "40") (name "Net-(P2-CW)") (class "Default")
      (node (ref "P2") (pin "2") (pinfunction "W_2") (pintype "passive"))
      (node (ref "P2") (pin "3") (pinfunction "CW_3") (pintype "passive"))
      (node (ref "R6") (pin "1") (pinfunction "1_1") (pintype "passive"))
    )
    (net (code "41") (name "Net-(T5A-S)") (class "Default")
      (node (ref "C26") (pin "1") (pinfunction "1_1") (pintype "passive"))
      (node (ref "R10") (pin "1") (pinfunction "1_1") (pintype "passive"))
      (node (ref "R11") (pin "2") (pinfunction "2_2") (pintype "passive"))
      (node (ref "SW4") (pin "2") (pinfunction "2_2") (pintype "passive"))
      (node (ref "T5") (pin "3") (pinfunction "S_3") (pintype "passive"))
    )
    (net (code "42") (name "P3V3") (class "Default")
      (node (ref "C7") (pin "2") (pinfunction "2_2") (pintype "passive"))
      (node (ref "D8") (pin "1") (pinfunction "C_1") (pintype "passive"))
      (node (ref "L2") (pin "2") (pinfunction "2_2") (pintype "passive"))
    )
    (net (code "43") (name "P12V0") (class "Default")
      (node (ref "C10") (pin "2") (pinfunction "2_2") (pintype "passive"))
      (node (ref "C12") (pin "1") (pinfunction "1_1") (pintype "passive"))
      (node (ref "C2") (pin "2") (pinfunction "2_2") (pintype "passive"))
      (node (ref "C20") (pin "1") (pinfunction "1_1") (pintype "passive"))
      (node (ref "C9") (pin "2") (pinfunction "2_2") (pintype "passive"))
      (node (ref "D1") (pin "1") (pinfunction "C_1") (pintype "passive"))
      (node (ref "D5") (pin "1") (pinfunction "C_1") (pintype "passive"))
      (node (ref "IC2") (pin "1") (pinfunction "VIN_1") (pintype "input"))
      (node (ref "IC8") (pin "6") (pinfunction "VCC_6") (pintype "power_in"))
      (node (ref "R20") (pin "2") (pinfunction "2_2") (pintype "passive"))
      (node (ref "R4") (pin "1") (pinfunction "1_1") (pintype "passive"))
      (node (ref "R46") (pin "2") (pinfunction "2_2") (pintype "passive"))
    )
    (net (code "44") (name "P12V0p") (class "Default")
      (node (ref "C22") (pin "1") (pinfunction "1_1") (pintype "passive"))
      (node (ref "C24") (pin "1") (pinfunction "1_1") (pintype "passive"))
      (node (ref "J3") (pin "1") (pinfunction "1_1") (pintype "bidirectional"))
      (node (ref "R21") (pin "2") (pinfunction "2_2") (pintype "passive"))
      (node (ref "T5") (pin "7") (pinfunction "D_7") (pintype "passive"))
      (node (ref "T5") (pin "8") (pinfunction "D_8") (pintype "passive"))
    )
    (net (code "45") (name "unconnected-(IC1-PFC_STOP-Pad9)") (class "Default")
      (node (ref "IC1") (pin "9") (pinfunction "PFC_STOP_9") (pintype "output"))
    )
    (net (code "46") (name "unconnected-(IC1-n.c.-Pad13)") (class "Default")
      (node (ref "IC1") (pin "13") (pinfunction "n.c._13") (pintype "passive"))
    )
    (net (code "47") (name "unconnected-(IC2-NC-Pad5)") (class "Default")
      (node (ref "IC2") (pin "5") (pinfunction "NC_5") (pintype "passive"))
    )
    (net (code "48") (name "unconnected-(IC2-NC-Pad8)") (class "Default")
      (node (ref "IC2") (pin "8") (pinfunction "NC_8") (pintype "passive"))
    )
    (net (code "49") (name "unconnected-(IC3-Boost-Pad1)") (class "Default")
      (node (ref "IC3") (pin "1") (pinfunction "Boost_1") (pintype "passive"))
    )
    (net (code "50") (name "unconnected-(IC3-LV-Pad6)") (class "Default")
      (node (ref "IC3") (pin "6") (pinfunction "LV_6") (pintype "output"))
    )
    (net (code "51") (name "unconnected-(IC3-OSC-Pad7)") (class "Default")
      (node (ref "IC3") (pin "7") (pinfunction "OSC_7") (pintype "passive"))
    )
  )
)
